# Morpheus_pill_bqle.net
KiCad netlist of a schematic drawn in Altium Designer
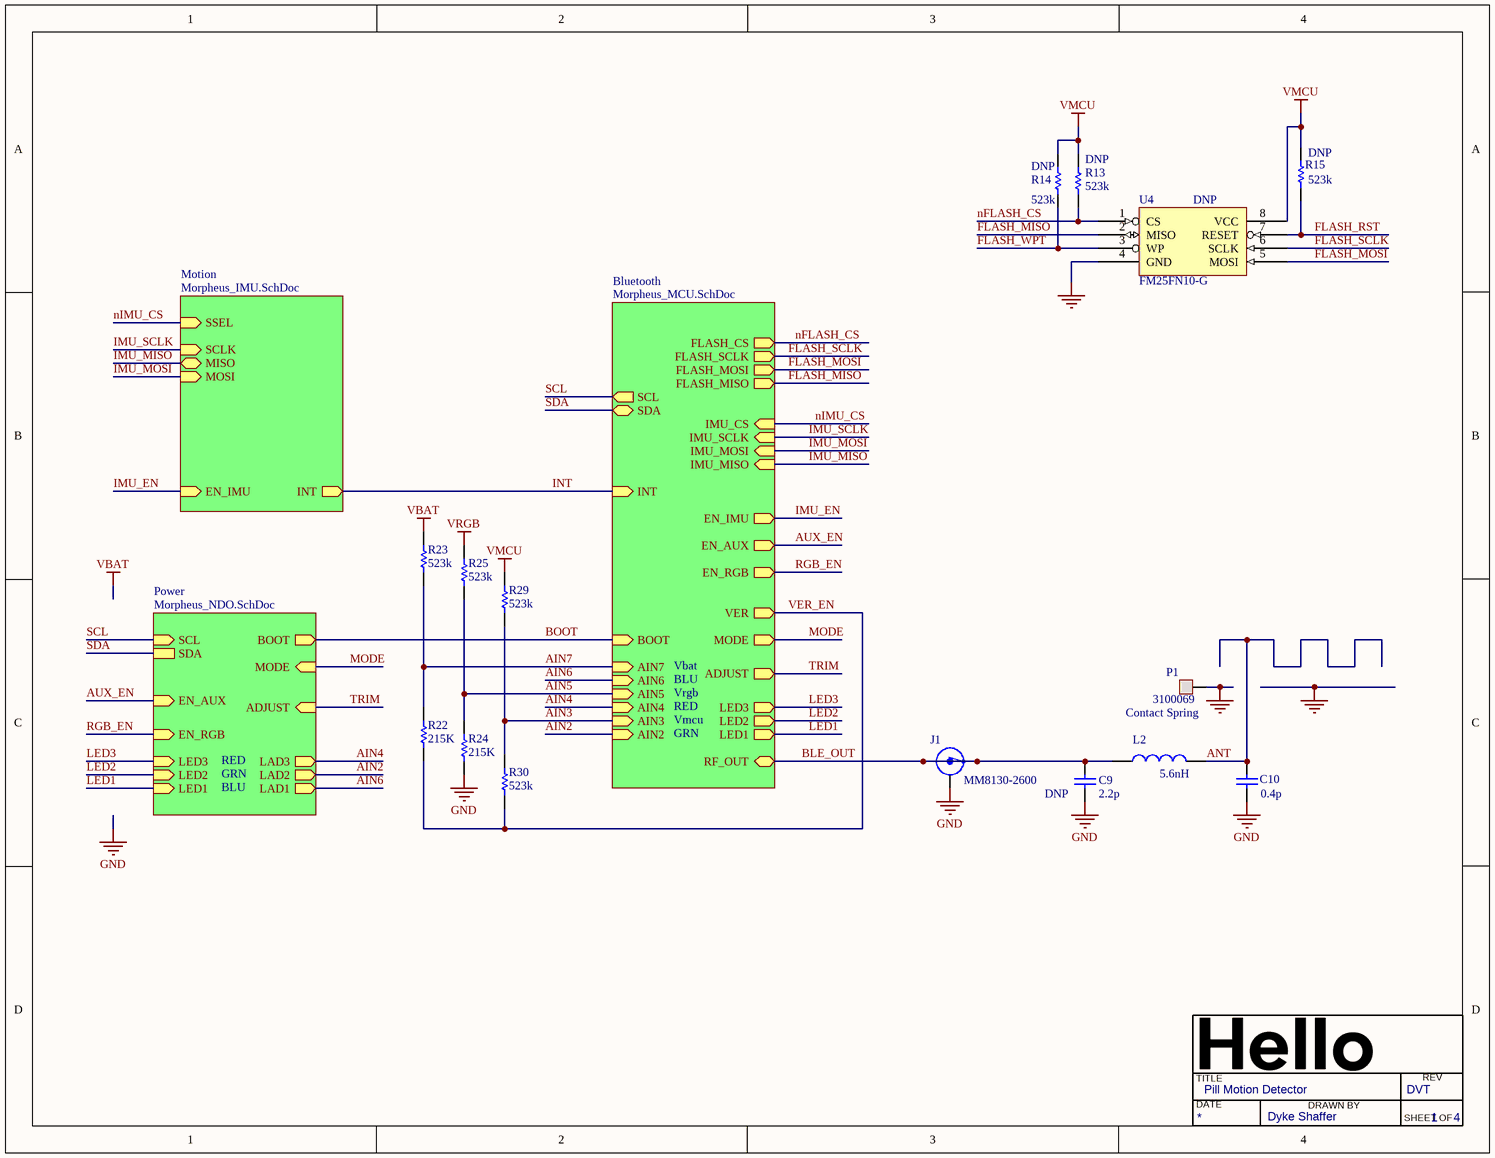
[diagram p0: Morpheus_pill_bqle.SchDoc]

(export (version "E")
  (design (tool "Eeschema 10.0.6"))
  (components
    (comp (ref "C9")
      (value "DNP")
      (footprint "CAP0402_SENSE_DVT")
      (description "Chip capacitor")
      (fields
        (field (name "ALTIUM_VALUE") "2.2p")
        (field (name "TOLERANCE") "5 %")
        (field (name "VOLTAGE") "50 V")
      )
      (libsource (lib "Hello") (part "C_2.2p_5_50_NPO_0402"))
    )
    (comp (ref "C10")
      (value "0.4p")
      (footprint "CAP0402_SENSE_DVT")
      (description "Chip capacitor")
      (fields (field (name "TOLERANCE") "5 %") (field (name "VOLTAGE") "50 V"))
      (libsource (lib "Hello") (part "C_0.4p_5_50_NPO_0402"))
    )
    (comp (ref "J1")
      (value "MM8130-2600")
      (footprint "COAXIAL-SWF")
      (description "Coaxial Connector with Switch")
      (fields
        (field (name "MANUFACTURER") "Murata")
        (field (name "2ND SOURCE PART NUMBER") "81-MM8130-2600RA2")
        (field (name "PUBLISHER") "Nordic Semiconductor")
      )
      (libsource (lib "Nordic Passive DB") (part "Coaxial-Internal-SW"))
    )
    (comp (ref "L2")
      (value "5.6nH")
      (footprint "IND_0402")
      (description "SMD RF inductor 2.2nH")
      (fields (field (name "TOLERANCE") "0.1"))
      (libsource (lib "Hello") (part "L_5.6n_0.1_?_270_300_?"))
    )
    (comp (ref "P1")
      (value "Contact Spring")
      (footprint "TP120X70SC")
      (description "Test Pad 120x70 mil ( contact spring )")
      (fields (field (name "PN") "3100069"))
      (libsource (lib "Hello") (part "TP-120X70-SC"))
    )
    (comp (ref "R13")
      (value "DNP")
      (footprint "RES0402_SENSE_DVT")
      (description "Chip Resistor")
      (fields
        (field (name "ALTIUM_VALUE") "523k")
        (field (name "TOLERANCE") "1 %")
        (field (name "POWER") "0.1 W")
      )
      (libsource (lib "Hello") (part "R_523k_1_0.1_0402"))
    )
    (comp (ref "R14")
      (value "DNP")
      (footprint "RES0402_SENSE_DVT")
      (description "Chip Resistor")
      (fields
        (field (name "ALTIUM_VALUE") "523k")
        (field (name "TOLERANCE") "1 %")
        (field (name "POWER") "0.1 W")
      )
      (libsource (lib "Hello") (part "R_523k_1_0.1_0402"))
    )
    (comp (ref "R15")
      (value "DNP")
      (footprint "RES0402_SENSE_DVT")
      (description "Chip Resistor")
      (fields
        (field (name "ALTIUM_VALUE") "523k")
        (field (name "TOLERANCE") "1 %")
        (field (name "POWER") "0.1 W")
      )
      (libsource (lib "Hello") (part "R_523k_1_0.1_0402"))
    )
    (comp (ref "R22")
      (value "215K")
      (footprint "RES0402_SENSE_DVT")
      (description "Chip Resistor")
      (fields (field (name "TOLERANCE") "1 %") (field (name "POWER") "0.1 W"))
      (libsource (lib "Hello") (part "R_215K_1_0.1_0402"))
    )
    (comp (ref "R23")
      (value "523k")
      (footprint "RES0402_SENSE_DVT")
      (description "Chip Resistor")
      (fields (field (name "TOLERANCE") "1 %") (field (name "POWER") "0.1 W"))
      (libsource (lib "Hello") (part "R_523k_1_0.1_0402"))
    )
    (comp (ref "R24")
      (value "215K")
      (footprint "RES0402_SENSE_DVT")
      (description "Chip Resistor")
      (fields (field (name "TOLERANCE") "1 %") (field (name "POWER") "0.1 W"))
      (libsource (lib "Hello") (part "R_215K_1_0.1_0402"))
    )
    (comp (ref "R25")
      (value "523k")
      (footprint "RES0402_SENSE_DVT")
      (description "Chip Resistor")
      (fields (field (name "TOLERANCE") "1 %") (field (name "POWER") "0.1 W"))
      (libsource (lib "Hello") (part "R_523k_1_0.1_0402"))
    )
    (comp (ref "R29")
      (value "523k")
      (footprint "RES0402_SENSE_DVT")
      (description "Chip Resistor")
      (fields (field (name "TOLERANCE") "1 %") (field (name "POWER") "0.1 W"))
      (libsource (lib "Hello") (part "R_523k_1_0.1_0402"))
    )
    (comp (ref "R30")
      (value "523k")
      (footprint "RES0402_SENSE_DVT")
      (description "Chip Resistor")
      (fields (field (name "TOLERANCE") "1 %") (field (name "POWER") "0.1 W"))
      (libsource (lib "Hello") (part "R_523k_1_0.1_0402"))
    )
    (comp (ref "U4")
      (value "DNP")
      (footprint "DFN127P600x500x80-8E")
      (description "Cypress SPI FRAM 128Kx8")
      (fields (field (name "PN") "FM25FN10-G"))
      (libsource (lib "dykes") (part "FM25VN10-G"))
    )
  )
  (nets
    (net (code "2") (name "/AIN3") (class "Default")
      (node (ref "R29") (pin "1") (pinfunction "1_1") (pintype "passive"))
      (node (ref "R30") (pin "2") (pinfunction "2_2") (pintype "passive"))
    )
    (net (code "4") (name "/AIN5") (class "Default")
      (node (ref "R24") (pin "2") (pinfunction "2_2") (pintype "passive"))
      (node (ref "R25") (pin "1") (pinfunction "1_1") (pintype "passive"))
    )
    (net (code "6") (name "/AIN7") (class "Default")
      (node (ref "R22") (pin "2") (pinfunction "2_2") (pintype "passive"))
      (node (ref "R23") (pin "1") (pinfunction "1_1") (pintype "passive"))
    )
    (net (code "7") (name "/ANT") (class "Default")
      (node (ref "C10") (pin "1") (pinfunction "1_1") (pintype "passive"))
      (node (ref "L2") (pin "2") (pintype "passive"))
    )
    (net (code "9") (name "/BLE_OUT") (class "Default")
      (node (ref "C9") (pin "1") (pinfunction "1_1") (pintype "passive"))
      (node (ref "J1") (pin "1") (pinfunction "IN_1") (pintype "passive"))
      (node (ref "J1") (pin "3") (pinfunction "OUT_3") (pintype "passive"))
      (node (ref "L2") (pin "1") (pintype "passive"))
    )
    (net (code "11") (name "/FLASH_MISO") (class "Default")
      (node (ref "U4") (pin "2") (pinfunction "MISO_2") (pintype "bidirectional"))
    )
    (net (code "12") (name "/FLASH_MOSI") (class "Default")
      (node (ref "U4") (pin "5") (pinfunction "MOSI_5") (pintype "input"))
    )
    (net (code "13") (name "/FLASH_RST") (class "Default")
      (node (ref "R15") (pin "1") (pinfunction "1_1") (pintype "passive"))
      (node (ref "U4") (pin "7") (pinfunction "RESET_7") (pintype "input"))
    )
    (net (code "14") (name "/FLASH_SCLK") (class "Default")
      (node (ref "U4") (pin "6") (pinfunction "SCLK_6") (pintype "input"))
    )
    (net (code "15") (name "/FLASH_WPT") (class "Default")
      (node (ref "R14") (pin "1") (pinfunction "1_1") (pintype "passive"))
      (node (ref "U4") (pin "3") (pinfunction "WP_3") (pintype "passive"))
    )
    (net (code "29") (name "/VER_EN") (class "Default")
      (node (ref "R22") (pin "1") (pinfunction "1_1") (pintype "passive"))
      (node (ref "R30") (pin "1") (pinfunction "1_1") (pintype "passive"))
    )
    (net (code "30") (name "/nFLASH_CS") (class "Default")
      (node (ref "R13") (pin "1") (pinfunction "1_1") (pintype "passive"))
      (node (ref "U4") (pin "1") (pinfunction "CS_1") (pintype "input"))
    )
    (net (code "32") (name "GND") (class "Default")
      (node (ref "C10") (pin "2") (pinfunction "2_2") (pintype "passive"))
      (node (ref "C9") (pin "2") (pinfunction "2_2") (pintype "passive"))
      (node (ref "J1") (pin "2") (pinfunction "Shield_2") (pintype "passive"))
      (node (ref "P1") (pin "1") (pinfunction "1_1") (pintype "passive"))
      (node (ref "R24") (pin "1") (pinfunction "1_1") (pintype "passive"))
      (node (ref "U4") (pin "4") (pinfunction "GND_4") (pintype "power_in"))
    )
    (net (code "33") (name "VBAT") (class "Default")
      (node (ref "R23") (pin "2") (pinfunction "2_2") (pintype "passive"))
    )
    (net (code "34") (name "VMCU") (class "Default")
      (node (ref "R13") (pin "2") (pinfunction "2_2") (pintype "passive"))
      (node (ref "R14") (pin "2") (pinfunction "2_2") (pintype "passive"))
      (node (ref "R15") (pin "2") (pinfunction "2_2") (pintype "passive"))
      (node (ref "R29") (pin "2") (pinfunction "2_2") (pintype "passive"))
      (node (ref "U4") (pin "8") (pinfunction "VCC_8") (pintype "power_in"))
    )
    (net (code "35") (name "VRGB") (class "Default")
      (node (ref "R25") (pin "2") (pinfunction "2_2") (pintype "passive"))
    )
  )
)
